# QuadLFO-Dev.net
KiCad netlist of a schematic drawn in EAGLE
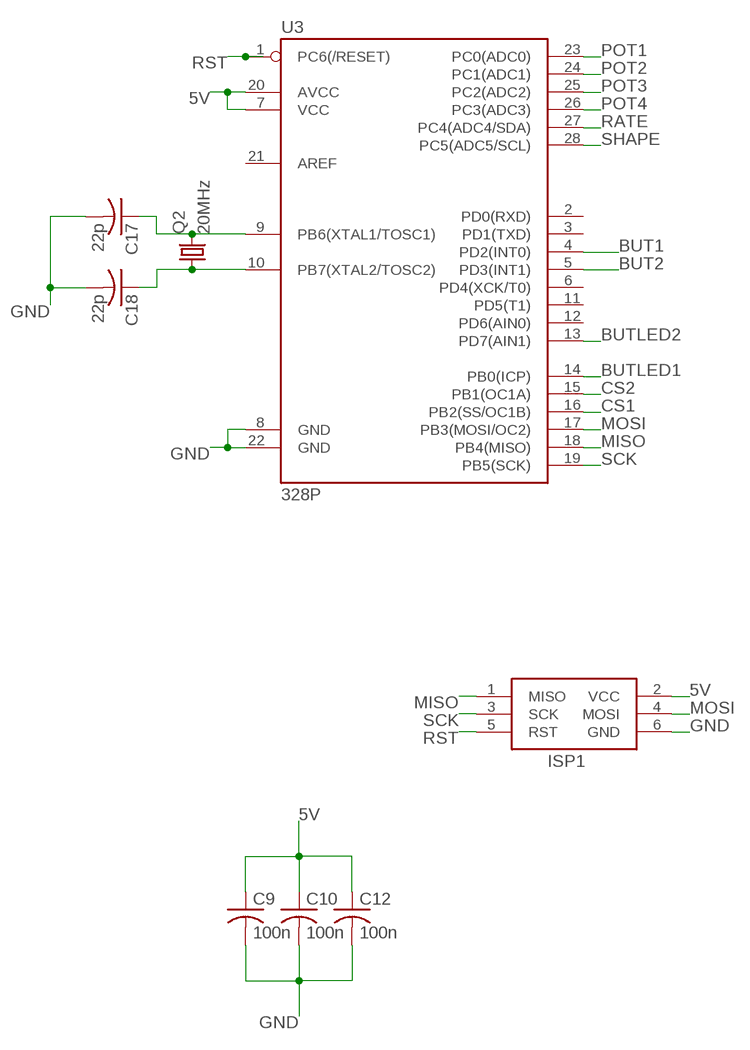
[diagram p0: schematic, sheet 1]
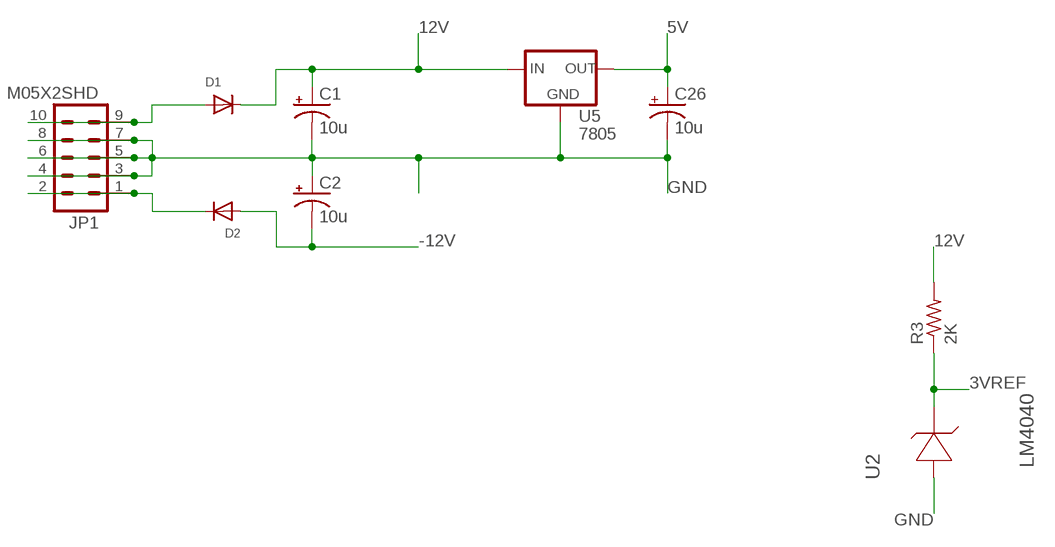
[diagram p1: schematic, sheet 2]
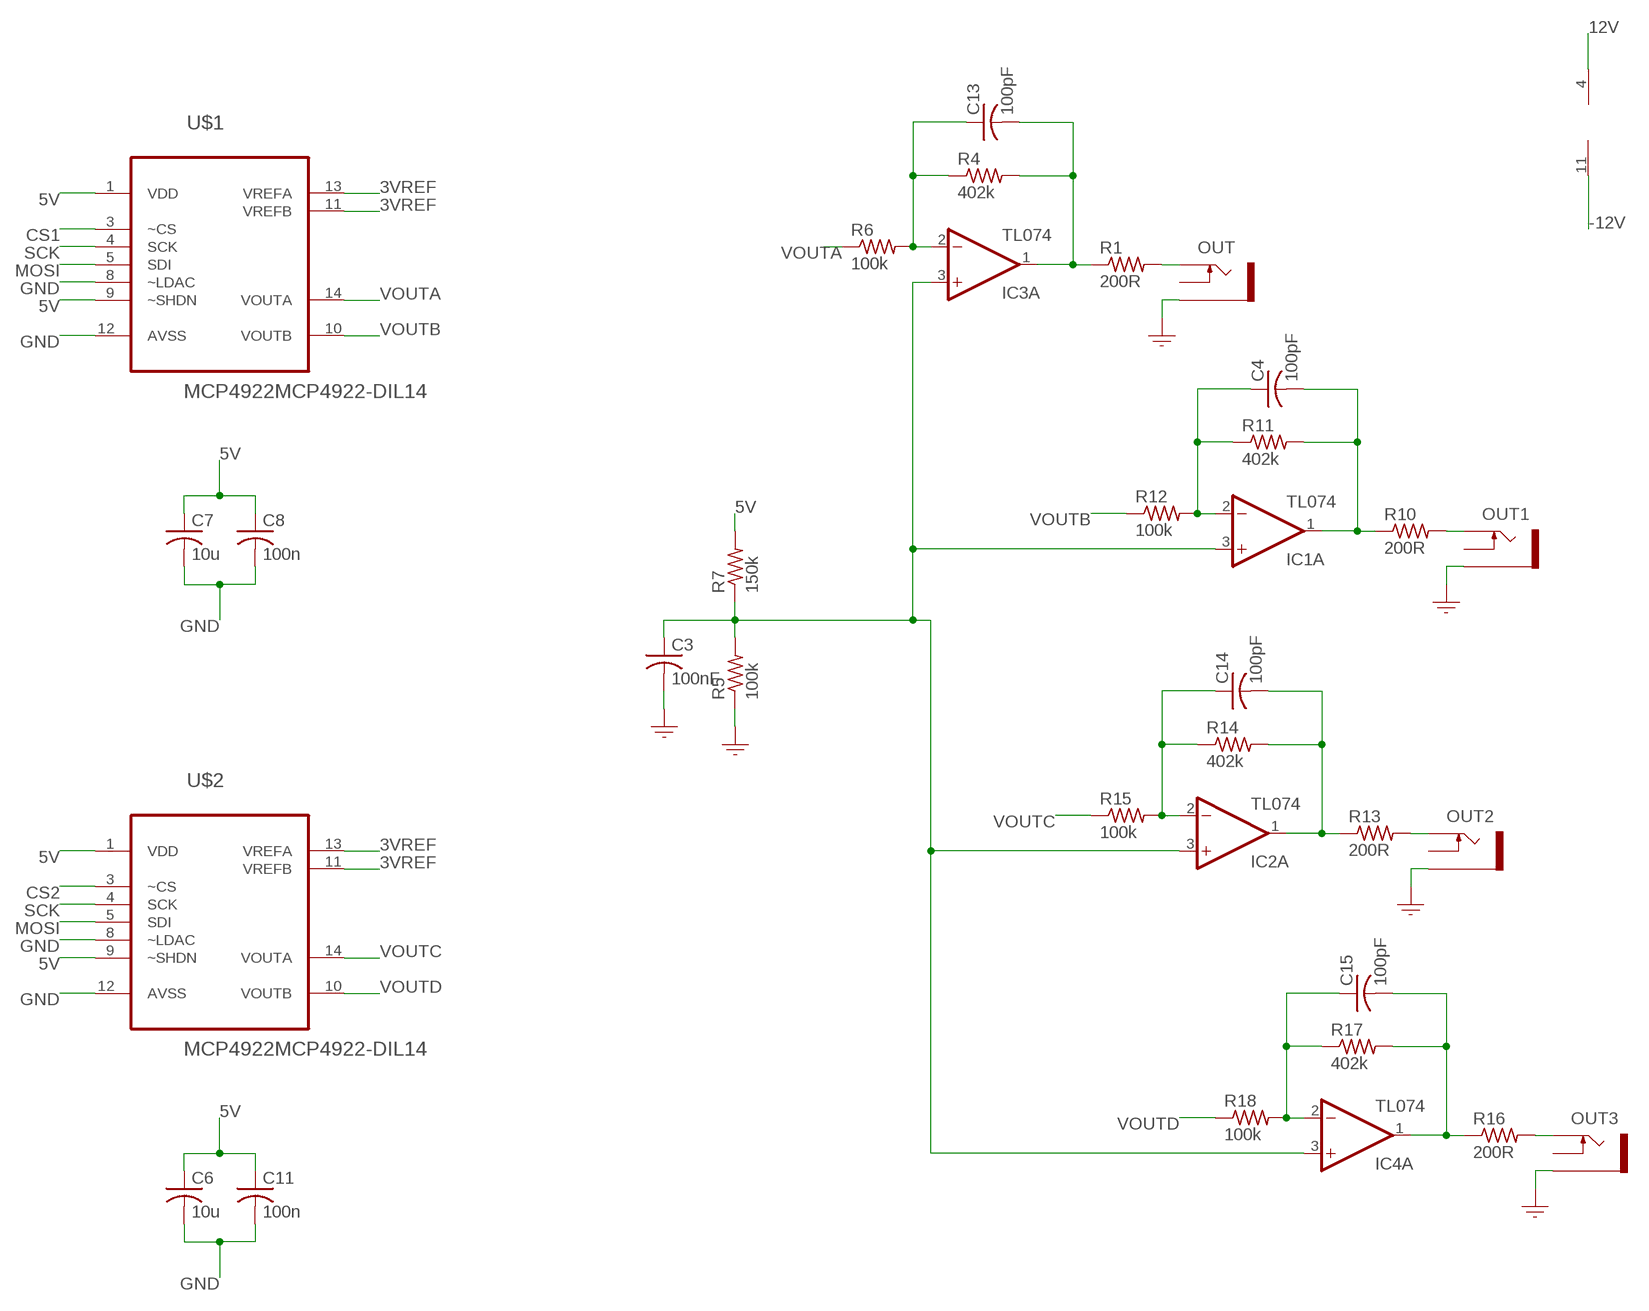
[diagram p2: schematic, sheet 3]
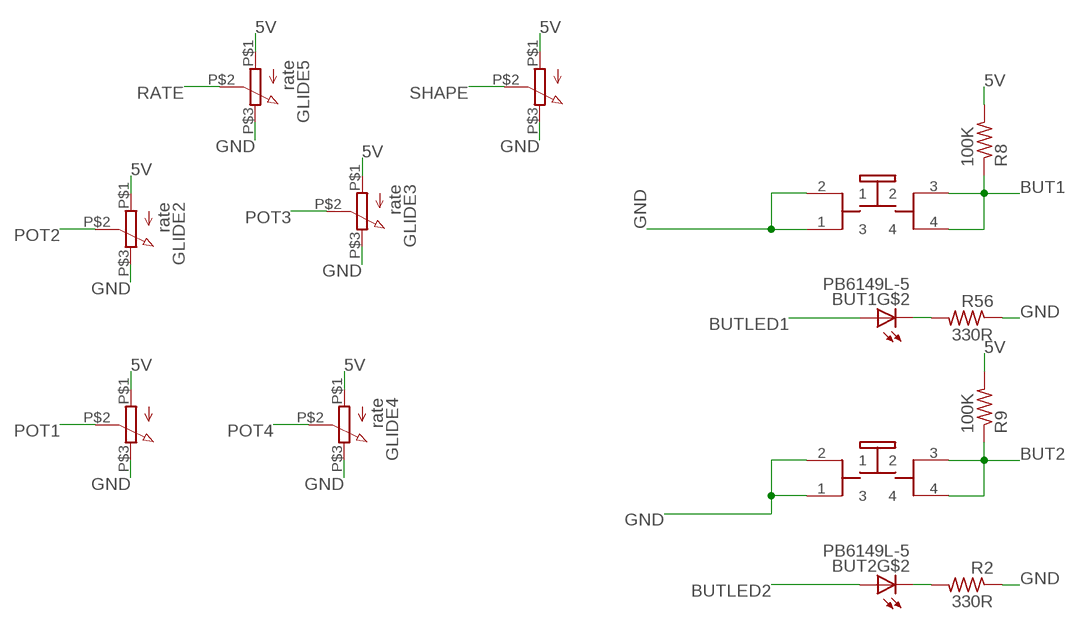
[diagram p3: schematic, sheet 4]

(export (version "E")
  (design (tool "Eeschema 10.0.6"))
  (components
    (comp (ref "C1")
      (value "10u")
      (footprint "eagle-import:153CLV-0505")
      (libsource (lib "eagle-import") (part "CPOL-US153CLV-0505"))
    )
    (comp (ref "C2")
      (value "10u")
      (footprint "eagle-import:153CLV-0505")
      (libsource (lib "eagle-import") (part "CPOL-US153CLV-0505"))
    )
    (comp (ref "C26")
      (value "10u")
      (footprint "eagle-import:153CLV-0505")
      (libsource (lib "eagle-import") (part "CPOL-US153CLV-0505"))
    )
    (comp (ref "D1")
      (value "DIODESMA")
      (footprint "eagle-import:SMADIODE")
      (libsource (lib "eagle-import") (part "DIODESMA"))
    )
    (comp (ref "D2")
      (value "DIODESMA")
      (footprint "eagle-import:SMADIODE")
      (libsource (lib "eagle-import") (part "DIODESMA"))
    )
    (comp (ref "JP1")
      (value "M05X2SHD")
      (footprint "eagle-import:2X5-SHROUDED")
      (libsource (lib "eagle-import") (part "M05X2SHD"))
    )
    (comp (ref "R3")
      (value "2K")
      (footprint "eagle-import:R0805")
      (libsource (lib "eagle-import") (part "R-US_R0805"))
    )
    (comp (ref "U2")
      (value "LM4040")
      (footprint "eagle-import:SOT95P237X112-3N")
      (fields (field (name "MPN") "LM4040A50IDBZT"))
      (libsource (lib "eagle-import") (part "LM4040A30IDBZT"))
    )
    (comp (ref "U5")
      (value "7805")
      (footprint "eagle-import:V-REG")
      (libsource (lib "eagle-import") (part "V-REG"))
    )
    (comp (ref "C3")
      (value "100nF")
      (footprint "eagle-import:C0805")
      (libsource (lib "eagle-import") (part "CAPACITOR-USC0805"))
    )
    (comp (ref "C4")
      (value "100pF")
      (footprint "eagle-import:C0805")
      (libsource (lib "eagle-import") (part "CAPACITOR-USC0805"))
    )
    (comp (ref "C6")
      (value "10u")
      (footprint "eagle-import:C0805K")
      (libsource (lib "eagle-import") (part "C-USC0805K"))
    )
    (comp (ref "C7")
      (value "10u")
      (footprint "eagle-import:C0805K")
      (libsource (lib "eagle-import") (part "C-USC0805K"))
    )
    (comp (ref "C8")
      (value "100n")
      (footprint "eagle-import:C0805K")
      (libsource (lib "eagle-import") (part "C-USC0805K"))
    )
    (comp (ref "C11")
      (value "100n")
      (footprint "eagle-import:C0805K")
      (libsource (lib "eagle-import") (part "C-USC0805K"))
    )
    (comp (ref "C13")
      (value "100pF")
      (footprint "eagle-import:C0805")
      (libsource (lib "eagle-import") (part "CAPACITOR-USC0805"))
    )
    (comp (ref "C14")
      (value "100pF")
      (footprint "eagle-import:C0805")
      (libsource (lib "eagle-import") (part "CAPACITOR-USC0805"))
    )
    (comp (ref "C15")
      (value "100pF")
      (footprint "eagle-import:C0805")
      (libsource (lib "eagle-import") (part "CAPACITOR-USC0805"))
    )
    (comp (ref "IC1")
      (value "TL074")
      (footprint "eagle-import:SO14")
      (libsource (lib "eagle-import") (part "OPAMP_QUADD"))
    )
    (comp (ref "IC2")
      (value "TL074")
      (footprint "eagle-import:SO14")
      (libsource (lib "eagle-import") (part "OPAMP_QUADD"))
    )
    (comp (ref "IC3")
      (value "TL074")
      (footprint "eagle-import:SO14")
      (libsource (lib "eagle-import") (part "OPAMP_QUADD"))
    )
    (comp (ref "IC4")
      (value "TL074")
      (footprint "eagle-import:SO14")
      (libsource (lib "eagle-import") (part "OPAMP_QUADD"))
    )
    (comp (ref "OUT")
      (value "PJ301M-12")
      (footprint "eagle-import:PJ301M-12")
      (libsource (lib "eagle-import") (part "SOCKET_MONO_3.5MMPJ301M-12"))
    )
    (comp (ref "OUT1")
      (value "PJ301M-12")
      (footprint "eagle-import:PJ301M-12")
      (libsource (lib "eagle-import") (part "SOCKET_MONO_3.5MMPJ301M-12"))
    )
    (comp (ref "OUT2")
      (value "PJ301M-12")
      (footprint "eagle-import:PJ301M-12")
      (libsource (lib "eagle-import") (part "SOCKET_MONO_3.5MMPJ301M-12"))
    )
    (comp (ref "OUT3")
      (value "PJ301M-12")
      (footprint "eagle-import:PJ301M-12")
      (libsource (lib "eagle-import") (part "SOCKET_MONO_3.5MMPJ301M-12"))
    )
    (comp (ref "R1")
      (value "200R")
      (footprint "eagle-import:R0805")
      (libsource (lib "eagle-import") (part "RESISTOR_USR0805"))
    )
    (comp (ref "R4")
      (value "402k")
      (footprint "eagle-import:R0805")
      (libsource (lib "eagle-import") (part "RESISTOR_USR0805"))
    )
    (comp (ref "R5")
      (value "100k")
      (footprint "eagle-import:R0805")
      (libsource (lib "eagle-import") (part "RESISTOR_USR0805"))
    )
    (comp (ref "R6")
      (value "100k")
      (footprint "eagle-import:R0805")
      (libsource (lib "eagle-import") (part "RESISTOR_USR0805"))
    )
    (comp (ref "R7")
      (value "150k")
      (footprint "eagle-import:R0805")
      (libsource (lib "eagle-import") (part "RESISTOR_USR0805"))
    )
    (comp (ref "R10")
      (value "200R")
      (footprint "eagle-import:R0805")
      (libsource (lib "eagle-import") (part "RESISTOR_USR0805"))
    )
    (comp (ref "R11")
      (value "402k")
      (footprint "eagle-import:R0805")
      (libsource (lib "eagle-import") (part "RESISTOR_USR0805"))
    )
    (comp (ref "R12")
      (value "100k")
      (footprint "eagle-import:R0805")
      (libsource (lib "eagle-import") (part "RESISTOR_USR0805"))
    )
    (comp (ref "R13")
      (value "200R")
      (footprint "eagle-import:R0805")
      (libsource (lib "eagle-import") (part "RESISTOR_USR0805"))
    )
    (comp (ref "R14")
      (value "402k")
      (footprint "eagle-import:R0805")
      (libsource (lib "eagle-import") (part "RESISTOR_USR0805"))
    )
    (comp (ref "R15")
      (value "100k")
      (footprint "eagle-import:R0805")
      (libsource (lib "eagle-import") (part "RESISTOR_USR0805"))
    )
    (comp (ref "R16")
      (value "200R")
      (footprint "eagle-import:R0805")
      (libsource (lib "eagle-import") (part "RESISTOR_USR0805"))
    )
    (comp (ref "R17")
      (value "402k")
      (footprint "eagle-import:R0805")
      (libsource (lib "eagle-import") (part "RESISTOR_USR0805"))
    )
    (comp (ref "R18")
      (value "100k")
      (footprint "eagle-import:R0805")
      (libsource (lib "eagle-import") (part "RESISTOR_USR0805"))
    )
    (comp (ref "U$1")
      (value "MCP4922MCP4922-DIL14")
      (footprint "eagle-import:DIL14")
      (libsource (lib "eagle-import") (part "MCP4922MCP4922-DIL14"))
    )
    (comp (ref "U$2")
      (value "MCP4922MCP4922-DIL14")
      (footprint "eagle-import:DIL14")
      (libsource (lib "eagle-import") (part "MCP4922MCP4922-DIL14"))
    )
    (comp (ref "C9")
      (value "100n")
      (footprint "eagle-import:C0805K")
      (libsource (lib "eagle-import") (part "C-USC0805K"))
    )
    (comp (ref "C10")
      (value "100n")
      (footprint "eagle-import:C0805K")
      (libsource (lib "eagle-import") (part "C-USC0805K"))
    )
    (comp (ref "C12")
      (value "100n")
      (footprint "eagle-import:C0805K")
      (libsource (lib "eagle-import") (part "C-USC0805K"))
    )
    (comp (ref "C17")
      (value "22p")
      (footprint "eagle-import:C0805K")
      (libsource (lib "eagle-import") (part "C-USC0805K"))
    )
    (comp (ref "C18")
      (value "22p")
      (footprint "eagle-import:C0805K")
      (libsource (lib "eagle-import") (part "C-USC0805K"))
    )
    (comp (ref "ISP1")
      (value "AVRISP-6")
      (footprint "eagle-import:AVRISP")
      (libsource (lib "eagle-import") (part "AVRISP-6"))
    )
    (comp (ref "Q2")
      (value "20MHz")
      (footprint "eagle-import:HC49UP")
      (libsource (lib "eagle-import") (part "CRYSTALHC49UP"))
    )
    (comp (ref "U3")
      (value "328P")
      (footprint "eagle-import:DIP28")
      (libsource (lib "eagle-import") (part "ATMEGA328P_PDIP"))
    )
    (comp (ref "BUT1")
      (value "PB6149L-5")
      (footprint "eagle-import:PB6149L")
      (libsource (lib "eagle-import") (part "PB6149L-5"))
    )
    (comp (ref "BUT2")
      (value "PB6149L-5")
      (footprint "eagle-import:PB6149L")
      (libsource (lib "eagle-import") (part "PB6149L-5"))
    )
    (comp (ref "GLIDE1")
      (value "rate")
      (footprint "eagle-import:POT")
      (libsource (lib "eagle-import") (part "9MMPOT"))
    )
    (comp (ref "GLIDE2")
      (value "rate")
      (footprint "eagle-import:POT")
      (libsource (lib "eagle-import") (part "9MMPOT"))
    )
    (comp (ref "GLIDE3")
      (value "rate")
      (footprint "eagle-import:POT")
      (libsource (lib "eagle-import") (part "9MMPOT"))
    )
    (comp (ref "GLIDE4")
      (value "rate")
      (footprint "eagle-import:POT")
      (libsource (lib "eagle-import") (part "9MMPOT"))
    )
    (comp (ref "GLIDE5")
      (value "rate")
      (footprint "eagle-import:POT")
      (libsource (lib "eagle-import") (part "9MMPOT"))
    )
    (comp (ref "GLIDE6")
      (value "rate")
      (footprint "eagle-import:POT")
      (libsource (lib "eagle-import") (part "9MMPOT"))
    )
    (comp (ref "R2")
      (value "330R")
      (footprint "eagle-import:R0805")
      (libsource (lib "eagle-import") (part "R-US_R0805"))
    )
    (comp (ref "R8")
      (value "100K")
      (footprint "eagle-import:R0805")
      (libsource (lib "eagle-import") (part "R-US_R0805"))
    )
    (comp (ref "R9")
      (value "100K")
      (footprint "eagle-import:R0805")
      (libsource (lib "eagle-import") (part "R-US_R0805"))
    )
    (comp (ref "R56")
      (value "330R")
      (footprint "eagle-import:R0805")
      (libsource (lib "eagle-import") (part "R-US_R0805"))
    )
  )
  (nets
    (net (code "1") (name "-12V") (class "Default")
      (node (ref "C2") (pin "-") (pinfunction "-_-") (pintype "passive"))
      (node (ref "D2") (pin "A") (pinfunction "A_A") (pintype "passive"))
      (node (ref "IC1") (pin "11") (pinfunction "V-_11") (pintype "power_in"))
    )
    (net (code "2") (name "3VREF") (class "Default")
      (node (ref "R3") (pin "1") (pinfunction "1_1") (pintype "passive"))
      (node (ref "U$1") (pin "11") (pinfunction "VREFB_11") (pintype "bidirectional"))
      (node (ref "U$1") (pin "13") (pinfunction "VREFA_13") (pintype "input"))
      (node (ref "U$2") (pin "11") (pinfunction "VREFB_11") (pintype "bidirectional"))
      (node (ref "U$2") (pin "13") (pinfunction "VREFA_13") (pintype "input"))
      (node (ref "U2") (pin "1") (pinfunction "CATHODE_1") (pintype "output"))
    )
    (net (code "3") (name "5V") (class "Default")
      (node (ref "C10") (pin "1") (pinfunction "1_1") (pintype "passive"))
      (node (ref "C11") (pin "1") (pinfunction "1_1") (pintype "passive"))
      (node (ref "C12") (pin "1") (pinfunction "1_1") (pintype "passive"))
      (node (ref "C26") (pin "+") (pinfunction "+_+") (pintype "passive"))
      (node (ref "C6") (pin "1") (pinfunction "1_1") (pintype "passive"))
      (node (ref "C7") (pin "1") (pinfunction "1_1") (pintype "passive"))
      (node (ref "C8") (pin "1") (pinfunction "1_1") (pintype "passive"))
      (node (ref "C9") (pin "1") (pinfunction "1_1") (pintype "passive"))
      (node (ref "GLIDE1") (pin "P$1") (pinfunction "1_P$1") (pintype "passive"))
      (node (ref "GLIDE2") (pin "P$1") (pinfunction "1_P$1") (pintype "passive"))
      (node (ref "GLIDE3") (pin "P$1") (pinfunction "1_P$1") (pintype "passive"))
      (node (ref "GLIDE4") (pin "P$1") (pinfunction "1_P$1") (pintype "passive"))
      (node (ref "GLIDE5") (pin "P$1") (pinfunction "1_P$1") (pintype "passive"))
      (node (ref "GLIDE6") (pin "P$1") (pinfunction "1_P$1") (pintype "passive"))
      (node (ref "ISP1") (pin "2") (pinfunction "VCC_2") (pintype "power_in"))
      (node (ref "R7") (pin "2") (pinfunction "2_2") (pintype "passive"))
      (node (ref "R8") (pin "2") (pinfunction "2_2") (pintype "passive"))
      (node (ref "R9") (pin "2") (pinfunction "2_2") (pintype "passive"))
      (node (ref "U$1") (pin "1") (pinfunction "VDD_1") (pintype "power_in"))
      (node (ref "U$1") (pin "9") (pinfunction "~{SHDN}_9") (pintype "bidirectional"))
      (node (ref "U$2") (pin "1") (pinfunction "VDD_1") (pintype "power_in"))
      (node (ref "U$2") (pin "9") (pinfunction "~{SHDN}_9") (pintype "bidirectional"))
      (node (ref "U3") (pin "20") (pinfunction "AVCC_20") (pintype "bidirectional"))
      (node (ref "U3") (pin "7") (pinfunction "VCC_7") (pintype "bidirectional"))
      (node (ref "U5") (pin "3") (pinfunction "OUT_3") (pintype "passive"))
    )
    (net (code "4") (name "12V") (class "Default")
      (node (ref "C1") (pin "+") (pinfunction "+_+") (pintype "passive"))
      (node (ref "D1") (pin "C") (pinfunction "C_C") (pintype "passive"))
      (node (ref "IC1") (pin "4") (pinfunction "V+_4") (pintype "power_in"))
      (node (ref "R3") (pin "2") (pinfunction "2_2") (pintype "passive"))
      (node (ref "U5") (pin "1") (pinfunction "IN_1") (pintype "input"))
    )
    (net (code "5") (name "BUT1") (class "Default")
      (node (ref "BUT1") (pin "3") (pinfunction "2_3") (pintype "bidirectional"))
      (node (ref "BUT1") (pin "4") (pinfunction "4_4") (pintype "bidirectional"))
      (node (ref "R8") (pin "1") (pinfunction "1_1") (pintype "passive"))
      (node (ref "U3") (pin "4") (pinfunction "PD2(INT0)_4") (pintype "bidirectional"))
    )
    (net (code "6") (name "BUT2") (class "Default")
      (node (ref "BUT2") (pin "3") (pinfunction "2_3") (pintype "bidirectional"))
      (node (ref "BUT2") (pin "4") (pinfunction "4_4") (pintype "bidirectional"))
      (node (ref "R9") (pin "1") (pinfunction "1_1") (pintype "passive"))
      (node (ref "U3") (pin "5") (pinfunction "PD3(INT1)_5") (pintype "bidirectional"))
    )
    (net (code "7") (name "BUTLED1") (class "Default")
      (node (ref "BUT1") (pin "A") (pinfunction "A_A") (pintype "passive"))
      (node (ref "U3") (pin "14") (pinfunction "PB0(ICP)_14") (pintype "bidirectional"))
    )
    (net (code "8") (name "BUTLED2") (class "Default")
      (node (ref "BUT2") (pin "A") (pinfunction "A_A") (pintype "passive"))
      (node (ref "U3") (pin "13") (pinfunction "PD7(AIN1)_13") (pintype "bidirectional"))
    )
    (net (code "9") (name "CS1") (class "Default")
      (node (ref "U$1") (pin "3") (pinfunction "~{CS}_3") (pintype "input"))
      (node (ref "U3") (pin "16") (pinfunction "PB2(SS/OC1B)_16") (pintype "bidirectional"))
    )
    (net (code "10") (name "CS2") (class "Default")
      (node (ref "U$2") (pin "3") (pinfunction "~{CS}_3") (pintype "input"))
      (node (ref "U3") (pin "15") (pinfunction "PB1(OC1A)_15") (pintype "bidirectional"))
    )
    (net (code "11") (name "GND") (class "Default")
      (node (ref "BUT1") (pin "1") (pinfunction "3_1") (pintype "bidirectional"))
      (node (ref "BUT1") (pin "2") (pinfunction "1_2") (pintype "bidirectional"))
      (node (ref "BUT2") (pin "1") (pinfunction "3_1") (pintype "bidirectional"))
      (node (ref "BUT2") (pin "2") (pinfunction "1_2") (pintype "bidirectional"))
      (node (ref "C1") (pin "-") (pinfunction "-_-") (pintype "passive"))
      (node (ref "C10") (pin "2") (pinfunction "2_2") (pintype "passive"))
      (node (ref "C11") (pin "2") (pinfunction "2_2") (pintype "passive"))
      (node (ref "C12") (pin "2") (pinfunction "2_2") (pintype "passive"))
      (node (ref "C17") (pin "2") (pinfunction "2_2") (pintype "passive"))
      (node (ref "C18") (pin "2") (pinfunction "2_2") (pintype "passive"))
      (node (ref "C2") (pin "+") (pinfunction "+_+") (pintype "passive"))
      (node (ref "C26") (pin "-") (pinfunction "-_-") (pintype "passive"))
      (node (ref "C3") (pin "2") (pinfunction "2_2") (pintype "passive"))
      (node (ref "C6") (pin "2") (pinfunction "2_2") (pintype "passive"))
      (node (ref "C7") (pin "2") (pinfunction "2_2") (pintype "passive"))
      (node (ref "C8") (pin "2") (pinfunction "2_2") (pintype "passive"))
      (node (ref "C9") (pin "2") (pinfunction "2_2") (pintype "passive"))
      (node (ref "GLIDE1") (pin "P$3") (pinfunction "3_P$3") (pintype "passive"))
      (node (ref "GLIDE2") (pin "P$3") (pinfunction "3_P$3") (pintype "passive"))
      (node (ref "GLIDE3") (pin "P$3") (pinfunction "3_P$3") (pintype "passive"))
      (node (ref "GLIDE4") (pin "P$3") (pinfunction "3_P$3") (pintype "passive"))
      (node (ref "GLIDE5") (pin "P$3") (pinfunction "3_P$3") (pintype "passive"))
      (node (ref "GLIDE6") (pin "P$3") (pinfunction "3_P$3") (pintype "passive"))
      (node (ref "ISP1") (pin "6") (pinfunction "GND_6") (pintype "power_in"))
      (node (ref "JP1") (pin "3") (pinfunction "3_3") (pintype "passive"))
      (node (ref "JP1") (pin "4") (pinfunction "4_4") (pintype "passive"))
      (node (ref "JP1") (pin "5") (pinfunction "5_5") (pintype "passive"))
      (node (ref "JP1") (pin "6") (pinfunction "6_6") (pintype "passive"))
      (node (ref "JP1") (pin "7") (pinfunction "7_7") (pintype "passive"))
      (node (ref "JP1") (pin "8") (pinfunction "8_8") (pintype "passive"))
      (node (ref "OUT") (pin "GND") (pinfunction "SLEEVE_GND") (pintype "passive"))
      (node (ref "OUT1") (pin "GND") (pinfunction "SLEEVE_GND") (pintype "passive"))
      (node (ref "OUT2") (pin "GND") (pinfunction "SLEEVE_GND") (pintype "passive"))
      (node (ref "OUT3") (pin "GND") (pinfunction "SLEEVE_GND") (pintype "passive"))
      (node (ref "R2") (pin "1") (pinfunction "1_1") (pintype "passive"))
      (node (ref "R5") (pin "1") (pinfunction "1_1") (pintype "passive"))
      (node (ref "R56") (pin "1") (pinfunction "1_1") (pintype "passive"))
      (node (ref "U$1") (pin "12") (pinfunction "AVSS_12") (pintype "passive"))
      (node (ref "U$1") (pin "8") (pinfunction "~{LDAC}_8") (pintype "input"))
      (node (ref "U$2") (pin "12") (pinfunction "AVSS_12") (pintype "passive"))
      (node (ref "U$2") (pin "8") (pinfunction "~{LDAC}_8") (pintype "input"))
      (node (ref "U2") (pin "2") (pinfunction "ANODE_2") (pintype "input"))
      (node (ref "U3") (pin "22") (pinfunction "GND_22") (pintype "bidirectional"))
      (node (ref "U3") (pin "8") (pinfunction "GND_8") (pintype "bidirectional"))
      (node (ref "U5") (pin "4") (pinfunction "GND_4") (pintype "input"))
    )
    (net (code "12") (name "MISO") (class "Default")
      (node (ref "ISP1") (pin "1") (pinfunction "MISO_1") (pintype "input"))
      (node (ref "U3") (pin "18") (pinfunction "PB4(MISO)_18") (pintype "bidirectional"))
    )
    (net (code "13") (name "MOSI") (class "Default")
      (node (ref "ISP1") (pin "4") (pinfunction "MOSI_4") (pintype "output"))
      (node (ref "U$1") (pin "5") (pinfunction "SDI_5") (pintype "input"))
      (node (ref "U$2") (pin "5") (pinfunction "SDI_5") (pintype "input"))
      (node (ref "U3") (pin "17") (pinfunction "PB3(MOSI/OC2)_17") (pintype "bidirectional"))
    )
    (net (code "14") (name "Net-(BUT1B-C)") (class "Default")
      (node (ref "BUT1") (pin "K") (pinfunction "C_K") (pintype "passive"))
      (node (ref "R56") (pin "2") (pinfunction "2_2") (pintype "passive"))
    )
    (net (code "15") (name "Net-(BUT2B-C)") (class "Default")
      (node (ref "BUT2") (pin "K") (pinfunction "C_K") (pintype "passive"))
      (node (ref "R2") (pin "2") (pinfunction "2_2") (pintype "passive"))
    )
    (net (code "16") (name "Net-(D1-PadA)") (class "Default")
      (node (ref "D1") (pin "A") (pinfunction "A_A") (pintype "passive"))
      (node (ref "JP1") (pin "10") (pinfunction "10_10") (pintype "passive"))
      (node (ref "JP1") (pin "9") (pinfunction "9_9") (pintype "passive"))
    )
    (net (code "17") (name "Net-(D2-PadC)") (class "Default")
      (node (ref "D2") (pin "C") (pinfunction "C_C") (pintype "passive"))
      (node (ref "JP1") (pin "1") (pinfunction "1_1") (pintype "passive"))
      (node (ref "JP1") (pin "2") (pinfunction "2_2") (pintype "passive"))
    )
    (net (code "18") (name "Net-(IC1A-+IN)") (class "Default")
      (node (ref "C3") (pin "1") (pinfunction "1_1") (pintype "passive"))
      (node (ref "IC1") (pin "3") (pinfunction "+IN_3") (pintype "input"))
      (node (ref "IC2") (pin "3") (pinfunction "+IN_3") (pintype "input"))
      (node (ref "IC3") (pin "3") (pinfunction "+IN_3") (pintype "input"))
      (node (ref "IC4") (pin "3") (pinfunction "+IN_3") (pintype "input"))
      (node (ref "R5") (pin "2") (pinfunction "2_2") (pintype "passive"))
      (node (ref "R7") (pin "1") (pinfunction "1_1") (pintype "passive"))
    )
    (net (code "19") (name "Net-(IC1A--IN)") (class "Default")
      (node (ref "C4") (pin "1") (pinfunction "1_1") (pintype "passive"))
      (node (ref "IC1") (pin "2") (pinfunction "-IN_2") (pintype "input"))
      (node (ref "R11") (pin "1") (pinfunction "1_1") (pintype "passive"))
      (node (ref "R12") (pin "2") (pinfunction "2_2") (pintype "passive"))
    )
    (net (code "20") (name "Net-(IC1A-OUT)") (class "Default")
      (node (ref "C4") (pin "2") (pinfunction "2_2") (pintype "passive"))
      (node (ref "IC1") (pin "1") (pinfunction "OUT_1") (pintype "output"))
      (node (ref "R10") (pin "1") (pinfunction "1_1") (pintype "passive"))
      (node (ref "R11") (pin "2") (pinfunction "2_2") (pintype "passive"))
    )
    (net (code "21") (name "Net-(IC2A--IN)") (class "Default")
      (node (ref "C14") (pin "1") (pinfunction "1_1") (pintype "passive"))
      (node (ref "IC2") (pin "2") (pinfunction "-IN_2") (pintype "input"))
      (node (ref "R14") (pin "1") (pinfunction "1_1") (pintype "passive"))
      (node (ref "R15") (pin "2") (pinfunction "2_2") (pintype "passive"))
    )
    (net (code "22") (name "Net-(IC2A-OUT)") (class "Default")
      (node (ref "C14") (pin "2") (pinfunction "2_2") (pintype "passive"))
      (node (ref "IC2") (pin "1") (pinfunction "OUT_1") (pintype "output"))
      (node (ref "R13") (pin "1") (pinfunction "1_1") (pintype "passive"))
      (node (ref "R14") (pin "2") (pinfunction "2_2") (pintype "passive"))
    )
    (net (code "23") (name "Net-(IC3A--IN)") (class "Default")
      (node (ref "C13") (pin "1") (pinfunction "1_1") (pintype "passive"))
      (node (ref "IC3") (pin "2") (pinfunction "-IN_2") (pintype "input"))
      (node (ref "R4") (pin "1") (pinfunction "1_1") (pintype "passive"))
      (node (ref "R6") (pin "2") (pinfunction "2_2") (pintype "passive"))
    )
    (net (code "24") (name "Net-(IC3A-OUT)") (class "Default")
      (node (ref "C13") (pin "2") (pinfunction "2_2") (pintype "passive"))
      (node (ref "IC3") (pin "1") (pinfunction "OUT_1") (pintype "output"))
      (node (ref "R1") (pin "1") (pinfunction "1_1") (pintype "passive"))
      (node (ref "R4") (pin "2") (pinfunction "2_2") (pintype "passive"))
    )
    (net (code "25") (name "Net-(IC4A--IN)") (class "Default")
      (node (ref "C15") (pin "1") (pinfunction "1_1") (pintype "passive"))
      (node (ref "IC4") (pin "2") (pinfunction "-IN_2") (pintype "input"))
      (node (ref "R17") (pin "1") (pinfunction "1_1") (pintype "passive"))
      (node (ref "R18") (pin "2") (pinfunction "2_2") (pintype "passive"))
    )
    (net (code "26") (name "Net-(IC4A-OUT)") (class "Default")
      (node (ref "C15") (pin "2") (pinfunction "2_2") (pintype "passive"))
      (node (ref "IC4") (pin "1") (pinfunction "OUT_1") (pintype "output"))
      (node (ref "R16") (pin "1") (pinfunction "1_1") (pintype "passive"))
      (node (ref "R17") (pin "2") (pinfunction "2_2") (pintype "passive"))
    )
    (net (code "27") (name "Net-(OUT-PadTIP)") (class "Default")
      (node (ref "OUT") (pin "TIP") (pinfunction "TIP_TIP") (pintype "passive"))
      (node (ref "R1") (pin "2") (pinfunction "2_2") (pintype "passive"))
    )
    (net (code "28") (name "Net-(OUT1-PadTIP)") (class "Default")
      (node (ref "OUT1") (pin "TIP") (pinfunction "TIP_TIP") (pintype "passive"))
      (node (ref "R10") (pin "2") (pinfunction "2_2") (pintype "passive"))
    )
    (net (code "29") (name "Net-(OUT2-PadTIP)") (class "Default")
      (node (ref "OUT2") (pin "TIP") (pinfunction "TIP_TIP") (pintype "passive"))
      (node (ref "R13") (pin "2") (pinfunction "2_2") (pintype "passive"))
    )
    (net (code "30") (name "Net-(OUT3-PadTIP)") (class "Default")
      (node (ref "OUT3") (pin "TIP") (pinfunction "TIP_TIP") (pintype "passive"))
      (node (ref "R16") (pin "2") (pinfunction "2_2") (pintype "passive"))
    )
    (net (code "31") (name "Net-(U3-PB6(XTAL1{slash}TOSC1))") (class "Default")
      (node (ref "C17") (pin "1") (pinfunction "1_1") (pintype "passive"))
      (node (ref "Q2") (pin "2") (pinfunction "2_2") (pintype "passive"))
      (node (ref "U3") (pin "9") (pinfunction "PB6(XTAL1/TOSC1)_9") (pintype "bidirectional"))
    )
    (net (code "32") (name "Net-(U3-PB7(XTAL2{slash}TOSC2))") (class "Default")
      (node (ref "C18") (pin "1") (pinfunction "1_1") (pintype "passive"))
      (node (ref "Q2") (pin "1") (pinfunction "1_1") (pintype "passive"))
      (node (ref "U3") (pin "10") (pinfunction "PB7(XTAL2/TOSC2)_10") (pintype "bidirectional"))
    )
    (net (code "33") (name "POT1") (class "Default")
      (node (ref "GLIDE1") (pin "P$2") (pinfunction "2_P$2") (pintype "passive"))
      (node (ref "U3") (pin "23") (pinfunction "PC0(ADC0)_23") (pintype "bidirectional"))
    )
    (net (code "34") (name "POT2") (class "Default")
      (node (ref "GLIDE2") (pin "P$2") (pinfunction "2_P$2") (pintype "passive"))
      (node (ref "U3") (pin "24") (pinfunction "PC1(ADC1)_24") (pintype "bidirectional"))
    )
    (net (code "35") (name "POT3") (class "Default")
      (node (ref "GLIDE3") (pin "P$2") (pinfunction "2_P$2") (pintype "passive"))
      (node (ref "U3") (pin "25") (pinfunction "PC2(ADC2)_25") (pintype "bidirectional"))
    )
    (net (code "36") (name "POT4") (class "Default")
      (node (ref "GLIDE4") (pin "P$2") (pinfunction "2_P$2") (pintype "passive"))
      (node (ref "U3") (pin "26") (pinfunction "PC3(ADC3)_26") (pintype "bidirectional"))
    )
    (net (code "37") (name "RATE") (class "Default")
      (node (ref "GLIDE5") (pin "P$2") (pinfunction "2_P$2") (pintype "passive"))
      (node (ref "U3") (pin "27") (pinfunction "PC4(ADC4/SDA)_27") (pintype "bidirectional"))
    )
    (net (code "38") (name "RST") (class "Default")
      (node (ref "ISP1") (pin "5") (pinfunction "RST_5") (pintype "output"))
      (node (ref "U3") (pin "1") (pinfunction "PC6(/RESET)_1") (pintype "bidirectional"))
    )
    (net (code "39") (name "SCK") (class "Default")
      (node (ref "ISP1") (pin "3") (pinfunction "SCK_3") (pintype "output"))
      (node (ref "U$1") (pin "4") (pinfunction "SCK_4") (pintype "input"))
      (node (ref "U$2") (pin "4") (pinfunction "SCK_4") (pintype "input"))
      (node (ref "U3") (pin "19") (pinfunction "PB5(SCK)_19") (pintype "bidirectional"))
    )
    (net (code "40") (name "SHAPE") (class "Default")
      (node (ref "GLIDE6") (pin "P$2") (pinfunction "2_P$2") (pintype "passive"))
      (node (ref "U3") (pin "28") (pinfunction "PC5(ADC5/SCL)_28") (pintype "bidirectional"))
    )
    (net (code "41") (name "VOUTA") (class "Default")
      (node (ref "R6") (pin "1") (pinfunction "1_1") (pintype "passive"))
      (node (ref "U$1") (pin "14") (pinfunction "VOUTA_14") (pintype "output"))
    )
    (net (code "42") (name "VOUTB") (class "Default")
      (node (ref "R12") (pin "1") (pinfunction "1_1") (pintype "passive"))
      (node (ref "U$1") (pin "10") (pinfunction "VOUTB_10") (pintype "output"))
    )
    (net (code "43") (name "VOUTC") (class "Default")
      (node (ref "R15") (pin "1") (pinfunction "1_1") (pintype "passive"))
      (node (ref "U$2") (pin "14") (pinfunction "VOUTA_14") (pintype "output"))
    )
    (net (code "44") (name "VOUTD") (class "Default")
      (node (ref "R18") (pin "1") (pinfunction "1_1") (pintype "passive"))
      (node (ref "U$2") (pin "10") (pinfunction "VOUTB_10") (pintype "output"))
    )
    (net (code "45") (name "unconnected-(OUT-SWITCH-PadNORM)") (class "Default")
      (node (ref "OUT") (pin "NORM") (pinfunction "SWITCH_NORM") (pintype "passive"))
    )
    (net (code "46") (name "unconnected-(OUT1-SWITCH-PadNORM)") (class "Default")
      (node (ref "OUT1") (pin "NORM") (pinfunction "SWITCH_NORM") (pintype "passive"))
    )
    (net (code "47") (name "unconnected-(OUT2-SWITCH-PadNORM)") (class "Default")
      (node (ref "OUT2") (pin "NORM") (pinfunction "SWITCH_NORM") (pintype "passive"))
    )
    (net (code "48") (name "unconnected-(OUT3-SWITCH-PadNORM)") (class "Default")
      (node (ref "OUT3") (pin "NORM") (pinfunction "SWITCH_NORM") (pintype "passive"))
    )
    (net (code "49") (name "unconnected-(U2-NC-Pad3)") (class "Default")
      (node (ref "U2") (pin "3") (pinfunction "NC_3") (pintype "no_connect"))
    )
    (net (code "50") (name "unconnected-(U3-AREF-Pad21)") (class "Default")
      (node (ref "U3") (pin "21") (pinfunction "AREF_21") (pintype "bidirectional"))
    )
    (net (code "51") (name "unconnected-(U3-PD0(RXD)-Pad2)") (class "Default")
      (node (ref "U3") (pin "2") (pinfunction "PD0(RXD)_2") (pintype "bidirectional"))
    )
    (net (code "52") (name "unconnected-(U3-PD1(TXD)-Pad3)") (class "Default")
      (node (ref "U3") (pin "3") (pinfunction "PD1(TXD)_3") (pintype "bidirectional"))
    )
    (net (code "53") (name "unconnected-(U3-PD4(XCK{slash}T0)-Pad6)") (class "Default")
      (node (ref "U3") (pin "6") (pinfunction "PD4(XCK/T0)_6") (pintype "bidirectional"))
    )
    (net (code "54") (name "unconnected-(U3-PD5(T1)-Pad11)") (class "Default")
      (node (ref "U3") (pin "11") (pinfunction "PD5(T1)_11") (pintype "bidirectional"))
    )
    (net (code "55") (name "unconnected-(U3-PD6(AIN0)-Pad12)") (class "Default")
      (node (ref "U3") (pin "12") (pinfunction "PD6(AIN0)_12") (pintype "bidirectional"))
    )
  )
)
